# CAN.net
KiCad netlist of a schematic drawn in Altium Designer
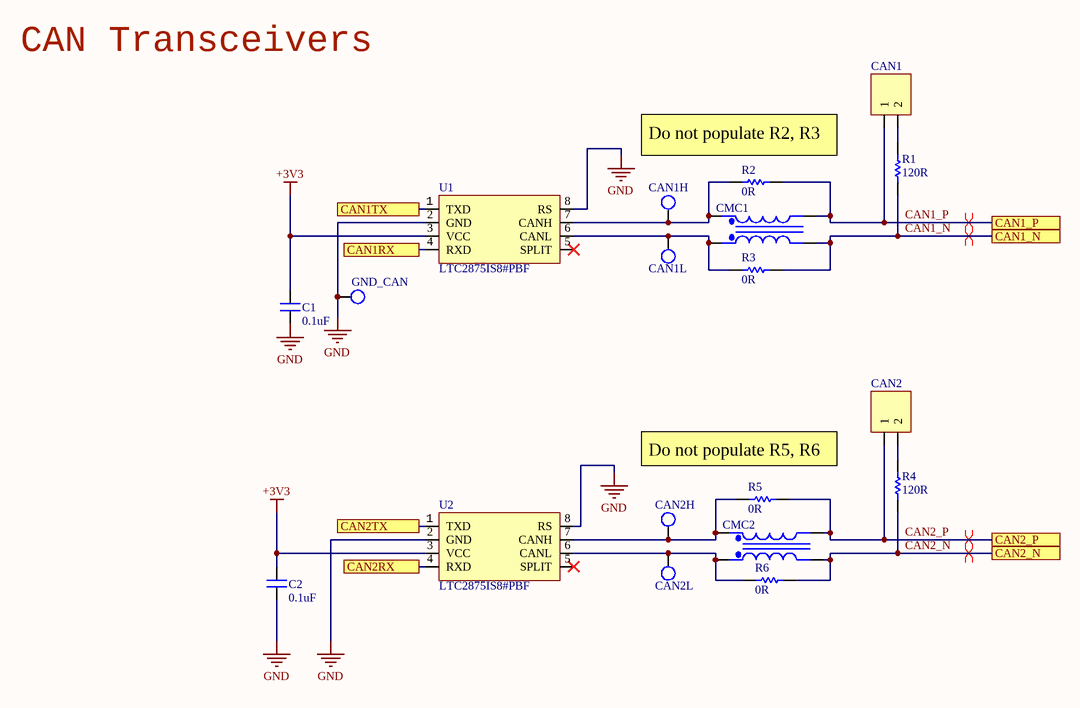
[diagram p0: CAN.SchDoc]

(export (version "E")
  (design (tool "Eeschema 10.0.6"))
  (components
    (comp (ref "C1")
      (value "0.1uF")
      (footprint "CAPC0603(1608)55_N")
      (description "CAP CER 0.1UF 50V X7R 0603")
      (fields (field (name "MPN") "CC0603KRX7R9BB104") (field (name "MANUFACTURER") "Yageo"))
      (libsource (lib "UWRT_Schematic_Library_2020") (part "CAP_0.1uF_50V_0603"))
    )
    (comp (ref "C2")
      (value "0.1uF")
      (footprint "CAPC0603(1608)55_N")
      (description "CAP CER 0.1UF 50V X7R 0603")
      (fields (field (name "MPN") "CC0603KRX7R9BB104") (field (name "MANUFACTURER") "Yageo"))
      (libsource (lib "UWRT_Schematic_Library_2020") (part "CAP_0.1uF_50V_0603"))
    )
    (comp (ref "CAN1")
      (value "JUMPER_2")
      (footprint "HDR1X2")
      (description "HEADER 2X1")
      (libsource (lib "UWRT_Schematic_Library_2020") (part "JUMPER_2"))
    )
    (comp (ref "CAN1H")
      (value "TESTPOINT_LOOP")
      (footprint "TESTPOINT_LOOP")
      (description "Loop testpoint through-hole pad")
      (fields (field (name "MANUFACTURER") "Keystone Electronics"))
      (libsource (lib "UWRT_Schematic_Library_2020") (part "TESTPOINT_LOOP"))
    )
    (comp (ref "CAN1L")
      (value "TESTPOINT_LOOP")
      (footprint "TESTPOINT_LOOP")
      (description "Loop testpoint through-hole pad")
      (fields (field (name "MANUFACTURER") "Keystone Electronics"))
      (libsource (lib "UWRT_Schematic_Library_2020") (part "TESTPOINT_LOOP"))
    )
    (comp (ref "CAN2")
      (value "JUMPER_2")
      (footprint "HDR1X2")
      (description "HEADER 2X1")
      (libsource (lib "UWRT_Schematic_Library_2020") (part "JUMPER_2"))
    )
    (comp (ref "CAN2H")
      (value "TESTPOINT_LOOP")
      (footprint "TESTPOINT_LOOP")
      (description "Loop testpoint through-hole pad")
      (fields (field (name "MANUFACTURER") "Keystone Electronics"))
      (libsource (lib "UWRT_Schematic_Library_2020") (part "TESTPOINT_LOOP"))
    )
    (comp (ref "CAN2L")
      (value "TESTPOINT_LOOP")
      (footprint "TESTPOINT_LOOP")
      (description "Loop testpoint through-hole pad")
      (fields (field (name "MANUFACTURER") "Keystone Electronics"))
      (libsource (lib "UWRT_Schematic_Library_2020") (part "TESTPOINT_LOOP"))
    )
    (comp (ref "CMC1")
      (value "CMC")
      (footprint "DR331-513AE")
      (description "Common Mode Choke")
      (fields (field (name "PUBLISHER") "Altium Limited"))
      (libsource (lib "UWRT_Schematic_Library_2020") (part "CMC"))
    )
    (comp (ref "CMC2")
      (value "CMC")
      (footprint "DR331-513AE")
      (description "Common Mode Choke")
      (fields (field (name "PUBLISHER") "Altium Limited"))
      (libsource (lib "UWRT_Schematic_Library_2020") (part "CMC"))
    )
    (comp (ref "GND_CAN")
      (value "TESTPOINT_LOOP")
      (footprint "TESTPOINT_LOOP")
      (description "Loop testpoint through-hole pad")
      (fields (field (name "MANUFACTURER") "Keystone Electronics"))
      (libsource (lib "UWRT_Schematic_Library_2020") (part "TESTPOINT_LOOP"))
    )
    (comp (ref "R1")
      (value "120R")
      (footprint "RESC0603(1608)_N")
      (description "RES SMD 120 OHM 5% 1/10W 0603")
      (fields (field (name "MANUFACTURER") "Yageo") (field (name "MPN") "RC0603JR-07120RL"))
      (libsource (lib "UWRT_Schematic_Library_2020") (part "RES_120R_0603"))
    )
    (comp (ref "R2")
      (value "0R")
      (footprint "RESC0603(1608)_N")
      (description "RES SMD 0 OHM JUMPER 1/10W 0603")
      (fields (field (name "MANUFACTURER") "Yageo") (field (name "MPN") "RC0603JR-070RL"))
      (libsource (lib "UWRT_Schematic_Library_2020") (part "RES_0R_0603"))
    )
    (comp (ref "R3")
      (value "0R")
      (footprint "RESC0603(1608)_N")
      (description "RES SMD 0 OHM JUMPER 1/10W 0603")
      (fields (field (name "MANUFACTURER") "Yageo") (field (name "MPN") "RC0603JR-070RL"))
      (libsource (lib "UWRT_Schematic_Library_2020") (part "RES_0R_0603"))
    )
    (comp (ref "R4")
      (value "120R")
      (footprint "RESC0603(1608)_N")
      (description "RES SMD 120 OHM 5% 1/10W 0603")
      (fields (field (name "MANUFACTURER") "Yageo") (field (name "MPN") "RC0603JR-07120RL"))
      (libsource (lib "UWRT_Schematic_Library_2020") (part "RES_120R_0603"))
    )
    (comp (ref "R5")
      (value "0R")
      (footprint "RESC0603(1608)_N")
      (description "RES SMD 0 OHM JUMPER 1/10W 0603")
      (fields (field (name "MANUFACTURER") "Yageo") (field (name "MPN") "RC0603JR-070RL"))
      (libsource (lib "UWRT_Schematic_Library_2020") (part "RES_0R_0603"))
    )
    (comp (ref "R6")
      (value "0R")
      (footprint "RESC0603(1608)_N")
      (description "RES SMD 0 OHM JUMPER 1/10W 0603")
      (fields (field (name "MANUFACTURER") "Yageo") (field (name "MPN") "RC0603JR-070RL"))
      (libsource (lib "UWRT_Schematic_Library_2020") (part "RES_0R_0603"))
    )
    (comp (ref "U1")
      (value "IC TXRX CAN")
      (footprint "LT-S8_N")
      (description "IC TXRX CAN 4MBPS 8SO")
      (fields (field (name "MANUFACTURER") "Linear Technologies") (field (name "MPN") "LTC2875IS8#PBF"))
      (libsource (lib "UWRT_Schematic_Library_2020") (part "LTC2875"))
    )
    (comp (ref "U2")
      (value "IC TXRX CAN")
      (footprint "LT-S8_N")
      (description "IC TXRX CAN 4MBPS 8SO")
      (fields (field (name "MANUFACTURER") "Linear Technologies") (field (name "MPN") "LTC2875IS8#PBF"))
      (libsource (lib "UWRT_Schematic_Library_2020") (part "LTC2875"))
    )
  )
  (nets
    (net (code "1") (name "+3V3") (class "Default")
      (node (ref "C1") (pin "2") (pinfunction "2_2") (pintype "passive"))
      (node (ref "C2") (pin "2") (pinfunction "2_2") (pintype "passive"))
      (node (ref "U1") (pin "3") (pinfunction "VCC_3") (pintype "passive"))
      (node (ref "U2") (pin "3") (pinfunction "VCC_3") (pintype "passive"))
    )
    (net (code "2") (name "/CAN1RX") (class "Default")
      (node (ref "U1") (pin "4") (pinfunction "RXD_4") (pintype "passive"))
    )
    (net (code "3") (name "/CAN1TX") (class "Default")
      (node (ref "U1") (pin "1") (pinfunction "TXD_1") (pintype "passive"))
    )
    (net (code "4") (name "/CAN1_N") (class "Default")
      (node (ref "CMC1") (pin "3") (pinfunction "Pri-_3") (pintype "passive"))
      (node (ref "R1") (pin "1") (pinfunction "1_1") (pintype "passive"))
      (node (ref "R3") (pin "2") (pinfunction "2_2") (pintype "passive"))
    )
    (net (code "5") (name "/CAN1_P") (class "Default")
      (node (ref "CAN1") (pin "1") (pinfunction "1_1") (pintype "passive"))
      (node (ref "CMC1") (pin "4") (pinfunction "Sec-_4") (pintype "passive"))
      (node (ref "R2") (pin "2") (pinfunction "2_2") (pintype "passive"))
    )
    (net (code "6") (name "/CAN2RX") (class "Default")
      (node (ref "U2") (pin "4") (pinfunction "RXD_4") (pintype "passive"))
    )
    (net (code "7") (name "/CAN2TX") (class "Default")
      (node (ref "U2") (pin "1") (pinfunction "TXD_1") (pintype "passive"))
    )
    (net (code "8") (name "/CAN2_N") (class "Default")
      (node (ref "CMC2") (pin "3") (pinfunction "Pri-_3") (pintype "passive"))
      (node (ref "R4") (pin "1") (pinfunction "1_1") (pintype "passive"))
      (node (ref "R6") (pin "2") (pinfunction "2_2") (pintype "passive"))
    )
    (net (code "9") (name "/CAN2_P") (class "Default")
      (node (ref "CAN2") (pin "1") (pinfunction "1_1") (pintype "passive"))
      (node (ref "CMC2") (pin "4") (pinfunction "Sec-_4") (pintype "passive"))
      (node (ref "R5") (pin "2") (pinfunction "2_2") (pintype "passive"))
    )
    (net (code "10") (name "GND") (class "Default")
      (node (ref "C1") (pin "1") (pinfunction "1_1") (pintype "passive"))
      (node (ref "C2") (pin "1") (pinfunction "1_1") (pintype "passive"))
      (node (ref "GND_CAN") (pin "1") (pintype "passive"))
      (node (ref "U1") (pin "2") (pinfunction "GND_2") (pintype "passive"))
      (node (ref "U1") (pin "8") (pinfunction "RS_8") (pintype "passive"))
      (node (ref "U2") (pin "2") (pinfunction "GND_2") (pintype "passive"))
      (node (ref "U2") (pin "8") (pinfunction "RS_8") (pintype "passive"))
    )
    (net (code "11") (name "Net-(CAN1-Pad2)") (class "Default")
      (node (ref "CAN1") (pin "2") (pinfunction "2_2") (pintype "passive"))
      (node (ref "R1") (pin "2") (pinfunction "2_2") (pintype "passive"))
    )
    (net (code "12") (name "Net-(CAN2-Pad2)") (class "Default")
      (node (ref "CAN2") (pin "2") (pinfunction "2_2") (pintype "passive"))
      (node (ref "R4") (pin "2") (pinfunction "2_2") (pintype "passive"))
    )
    (net (code "13") (name "Net-(CMC1-Pri+)") (class "Default")
      (node (ref "CAN1L") (pin "1") (pintype "passive"))
      (node (ref "CMC1") (pin "2") (pinfunction "Pri+_2") (pintype "passive"))
      (node (ref "R3") (pin "1") (pinfunction "1_1") (pintype "passive"))
      (node (ref "U1") (pin "6") (pinfunction "CANL_6") (pintype "passive"))
    )
    (net (code "14") (name "Net-(CMC1-Sec+)") (class "Default")
      (node (ref "CAN1H") (pin "1") (pintype "passive"))
      (node (ref "CMC1") (pin "1") (pinfunction "Sec+_1") (pintype "passive"))
      (node (ref "R2") (pin "1") (pinfunction "1_1") (pintype "passive"))
      (node (ref "U1") (pin "7") (pinfunction "CANH_7") (pintype "passive"))
    )
    (net (code "15") (name "Net-(CMC2-Pri+)") (class "Default")
      (node (ref "CAN2L") (pin "1") (pintype "passive"))
      (node (ref "CMC2") (pin "2") (pinfunction "Pri+_2") (pintype "passive"))
      (node (ref "R6") (pin "1") (pinfunction "1_1") (pintype "passive"))
      (node (ref "U2") (pin "6") (pinfunction "CANL_6") (pintype "passive"))
    )
    (net (code "16") (name "Net-(CMC2-Sec+)") (class "Default")
      (node (ref "CAN2H") (pin "1") (pintype "passive"))
      (node (ref "CMC2") (pin "1") (pinfunction "Sec+_1") (pintype "passive"))
      (node (ref "R5") (pin "1") (pinfunction "1_1") (pintype "passive"))
      (node (ref "U2") (pin "7") (pinfunction "CANH_7") (pintype "passive"))
    )
    (net (code "17") (name "unconnected-(U1-SPLIT-Pad5)") (class "Default")
      (node (ref "U1") (pin "5") (pinfunction "SPLIT_5") (pintype "passive+no_connect"))
    )
    (net (code "18") (name "unconnected-(U2-SPLIT-Pad5)") (class "Default")
      (node (ref "U2") (pin "5") (pinfunction "SPLIT_5") (pintype "passive+no_connect"))
    )
  )
)
